# main_scheme.net
KiCad netlist of a schematic drawn in Altium Designer
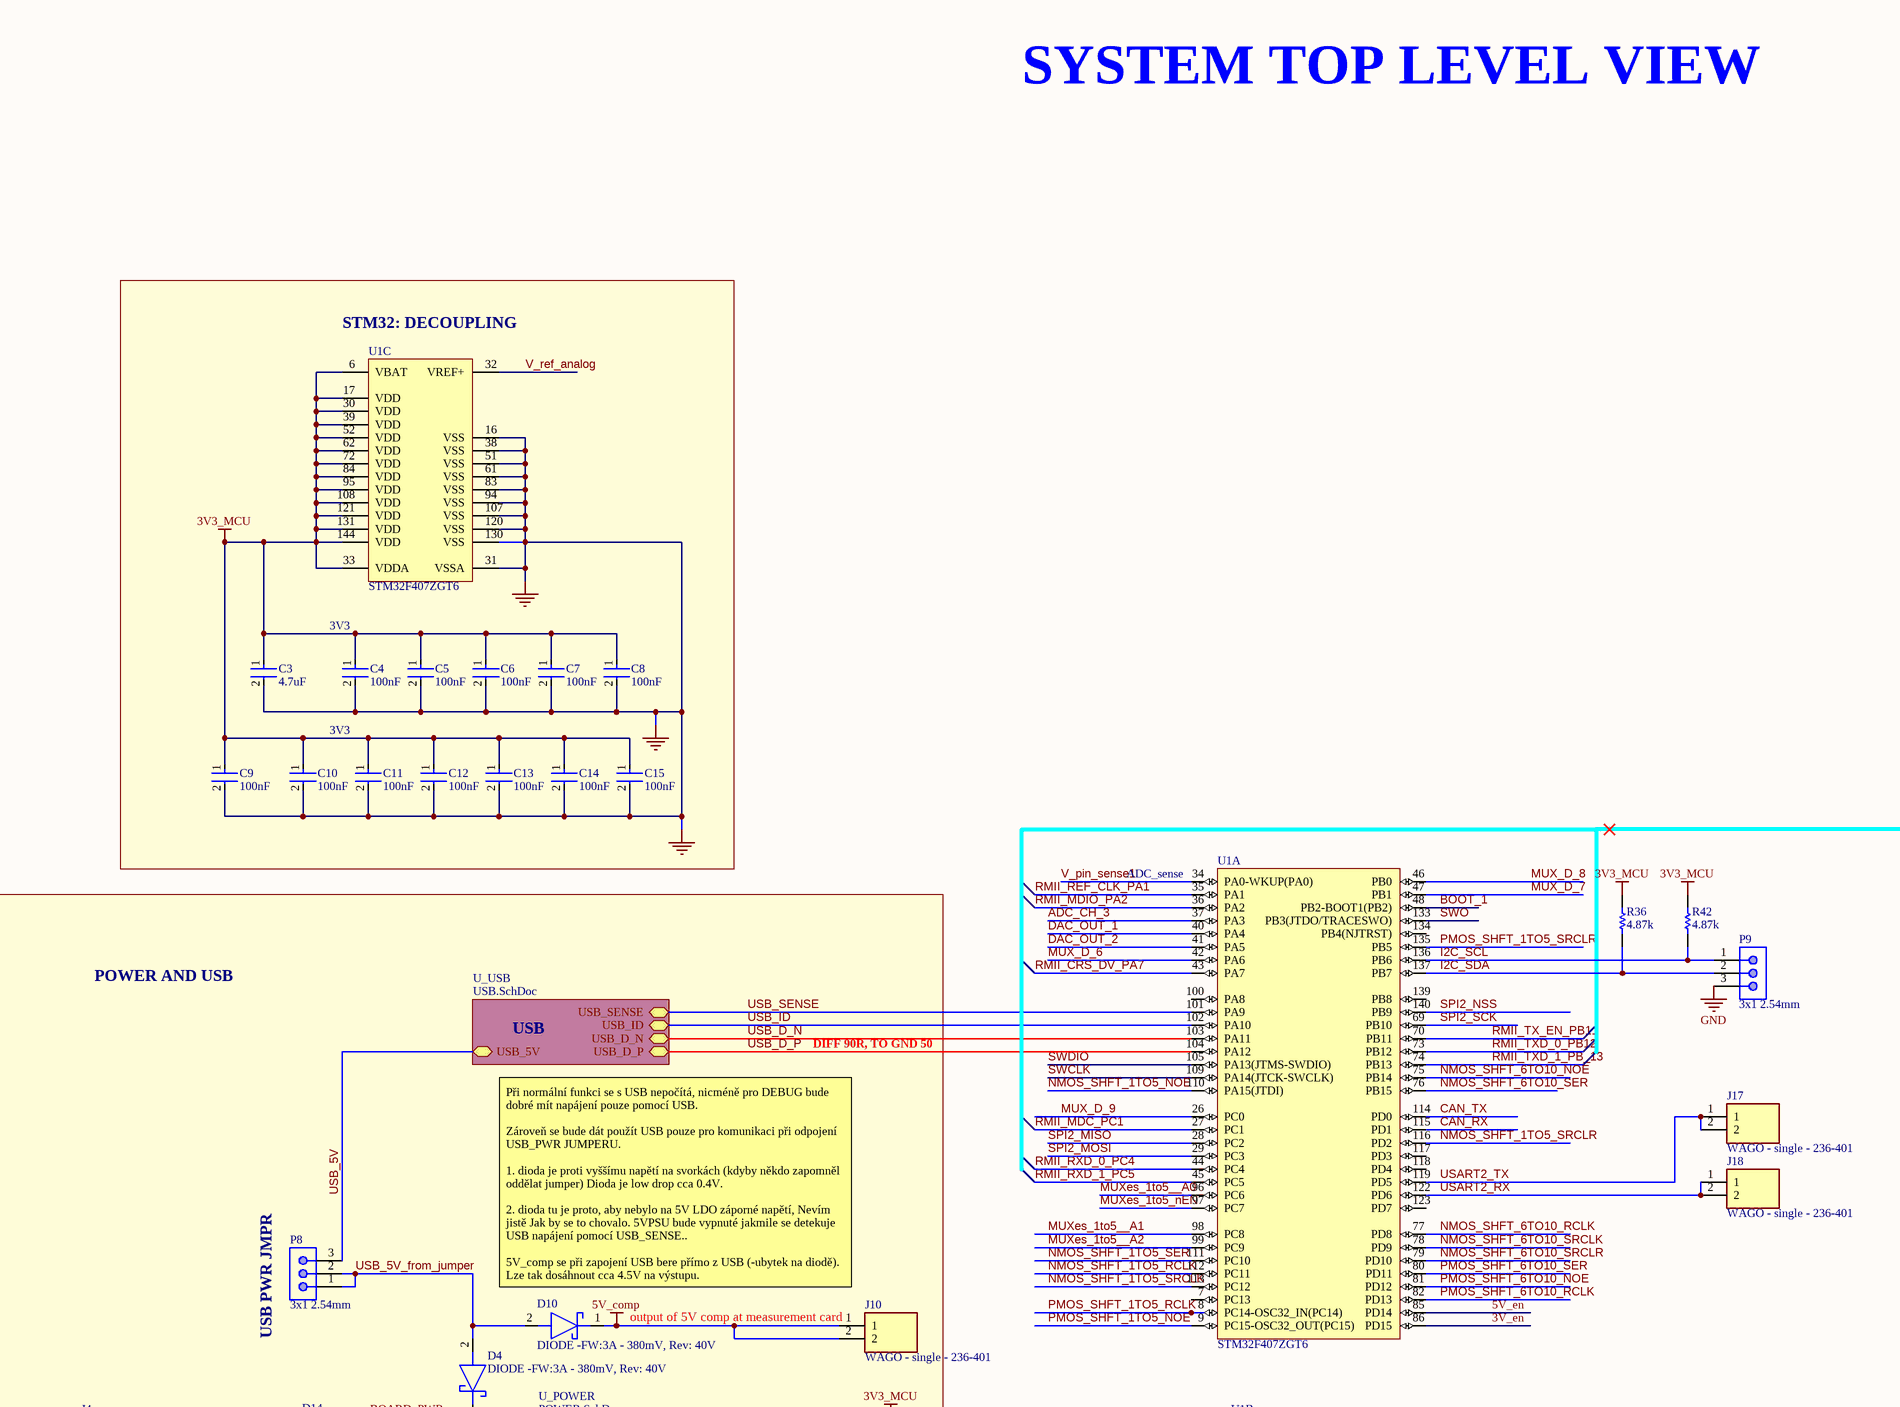
[diagram p0: main_scheme.SchDoc, top left]
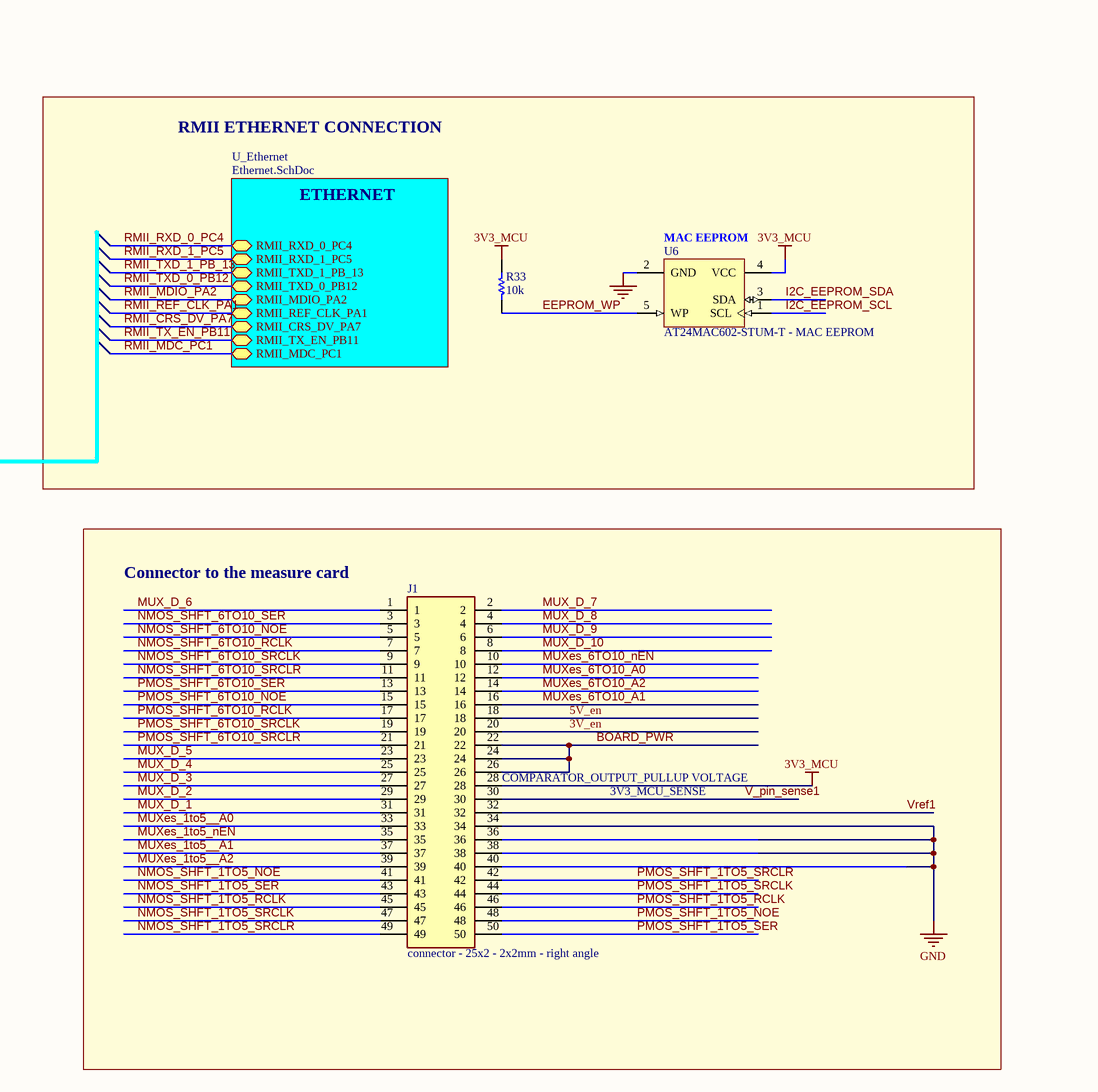
[diagram p1: main_scheme.SchDoc, top right]
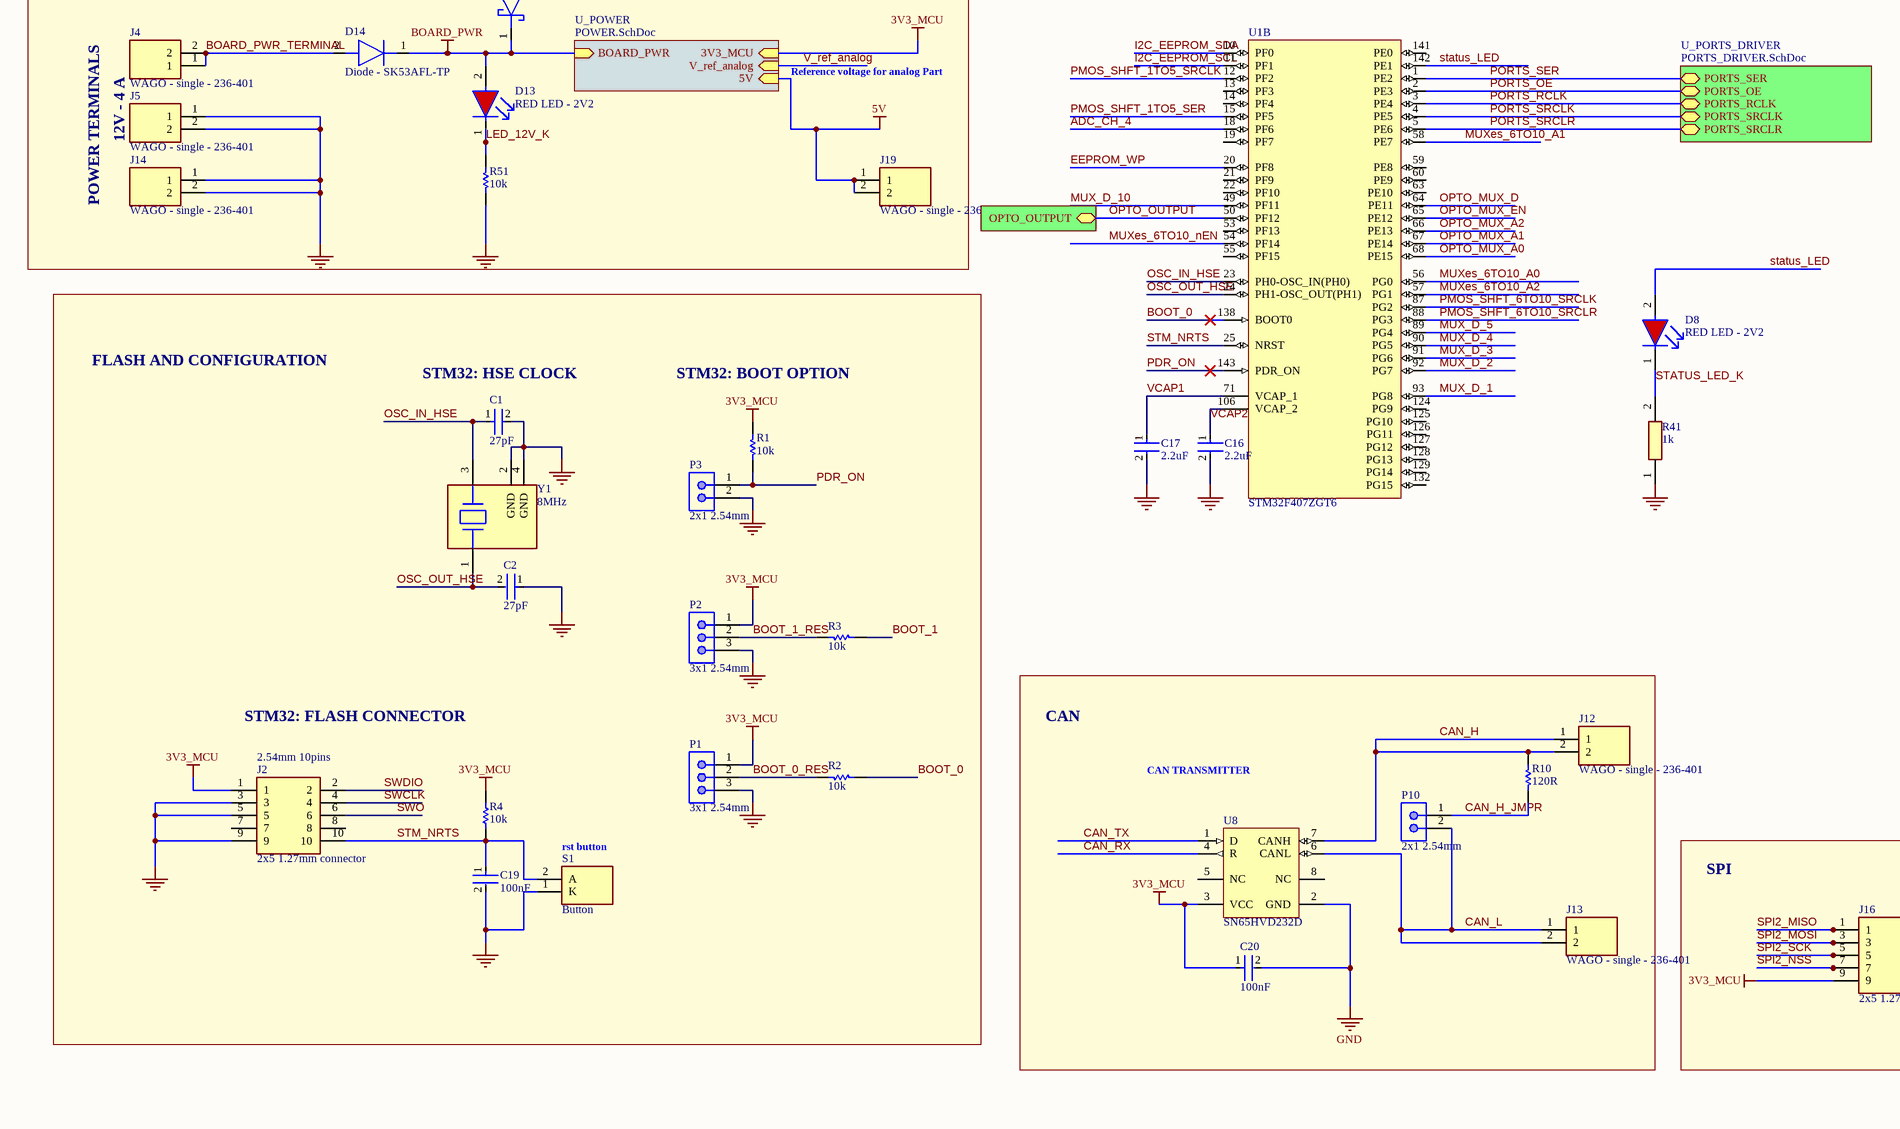
[diagram p2: main_scheme.SchDoc, bottom left]
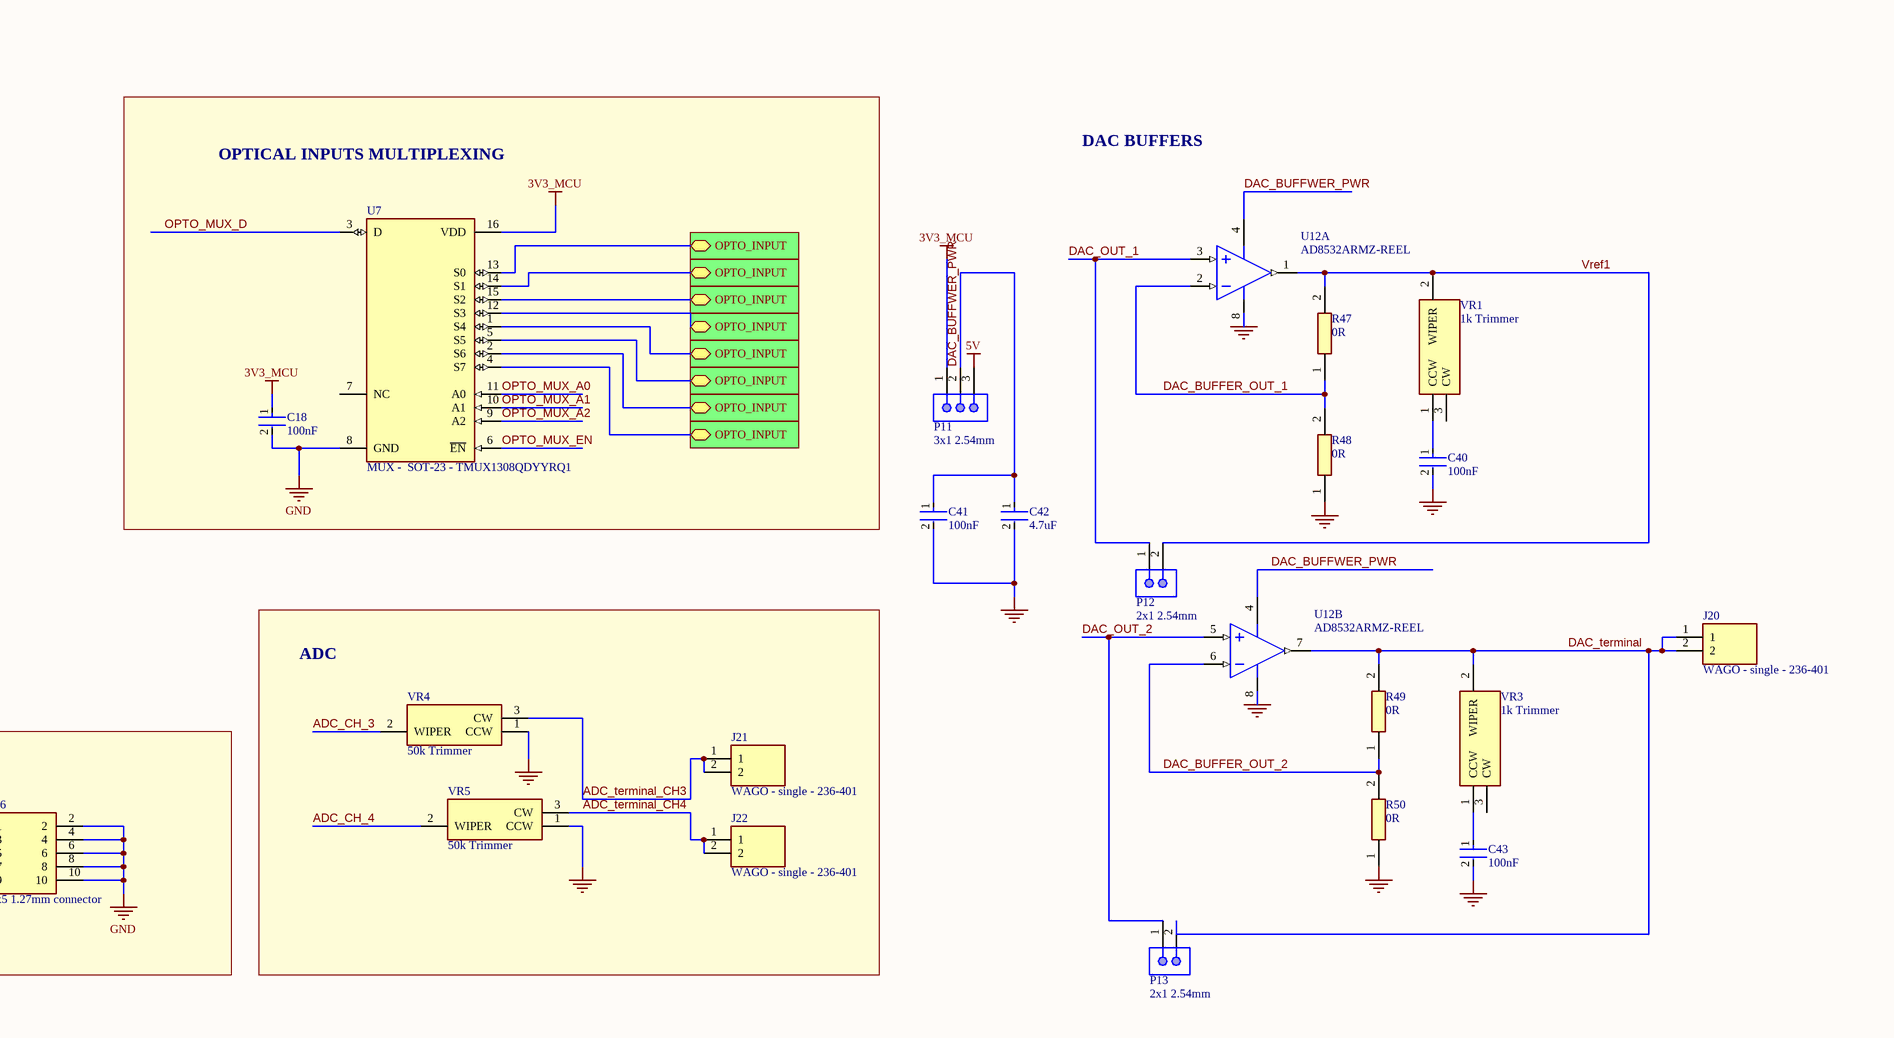
[diagram p3: main_scheme.SchDoc, bottom right]

(export (version "E")
  (design (tool "Eeschema 10.0.6"))
  (components
    (comp (ref "C1")
      (value "27pF")
      (footprint "0402 CAP")
      (description "Cap Ceramic 0402, 27pF, 25V,10%")
      (fields (field (name "PARTNUMBER") "C0402C270K3GACTU"))
      (libsource (lib "Schlib1") (part "CAP 0402 - 27pF"))
    )
    (comp (ref "C2")
      (value "27pF")
      (footprint "0402 CAP")
      (description "Cap Ceramic 0402, 27pF, 25V,10%")
      (fields (field (name "PARTNUMBER") "C0402C270K3GACTU"))
      (libsource (lib "Schlib1") (part "CAP 0402 - 27pF"))
    )
    (comp (ref "C3")
      (value "4.7uF")
      (footprint "0603-CAP")
      (description "General Purpose Ceramic Capacitor, 0603,4.7uF,35V,10%")
      (fields (field (name "PARTNUMBER") "C1608X5R1V475K080AC"))
      (libsource (lib "Schlib1") (part "CAP-0603-4.7uF"))
    )
    (comp (ref "C4")
      (value "100nF")
      (footprint "0402 CAP")
      (description "Cap Ceramic 0402,0.1uF, 25V,10%")
      (fields (field (name "PARTNUMBER") "C0402C104K3RACTU"))
      (libsource (lib "Schlib1") (part "CAP 0402 - 100nF"))
    )
    (comp (ref "C5")
      (value "100nF")
      (footprint "0402 CAP")
      (description "Cap Ceramic 0402,0.1uF, 25V,10%")
      (fields (field (name "PARTNUMBER") "C0402C104K3RACTU"))
      (libsource (lib "Schlib1") (part "CAP 0402 - 100nF"))
    )
    (comp (ref "C6")
      (value "100nF")
      (footprint "0402 CAP")
      (description "Cap Ceramic 0402,0.1uF, 25V,10%")
      (fields (field (name "PARTNUMBER") "C0402C104K3RACTU"))
      (libsource (lib "Schlib1") (part "CAP 0402 - 100nF"))
    )
    (comp (ref "C7")
      (value "100nF")
      (footprint "0402 CAP")
      (description "Cap Ceramic 0402,0.1uF, 25V,10%")
      (fields (field (name "PARTNUMBER") "C0402C104K3RACTU"))
      (libsource (lib "Schlib1") (part "CAP 0402 - 100nF"))
    )
    (comp (ref "C8")
      (value "100nF")
      (footprint "0402 CAP")
      (description "Cap Ceramic 0402,0.1uF, 25V,10%")
      (fields (field (name "PARTNUMBER") "C0402C104K3RACTU"))
      (libsource (lib "Schlib1") (part "CAP 0402 - 100nF"))
    )
    (comp (ref "C9")
      (value "100nF")
      (footprint "0402 CAP")
      (description "Cap Ceramic 0402,0.1uF, 25V,10%")
      (fields (field (name "PARTNUMBER") "C0402C104K3RACTU"))
      (libsource (lib "Schlib1") (part "CAP 0402 - 100nF"))
    )
    (comp (ref "C10")
      (value "100nF")
      (footprint "0402 CAP")
      (description "Cap Ceramic 0402,0.1uF, 25V,10%")
      (fields (field (name "PARTNUMBER") "C0402C104K3RACTU"))
      (libsource (lib "Schlib1") (part "CAP 0402 - 100nF"))
    )
    (comp (ref "C11")
      (value "100nF")
      (footprint "0402 CAP")
      (description "Cap Ceramic 0402,0.1uF, 25V,10%")
      (fields (field (name "PARTNUMBER") "C0402C104K3RACTU"))
      (libsource (lib "Schlib1") (part "CAP 0402 - 100nF"))
    )
    (comp (ref "C12")
      (value "100nF")
      (footprint "0402 CAP")
      (description "Cap Ceramic 0402,0.1uF, 25V,10%")
      (fields (field (name "PARTNUMBER") "C0402C104K3RACTU"))
      (libsource (lib "Schlib1") (part "CAP 0402 - 100nF"))
    )
    (comp (ref "C13")
      (value "100nF")
      (footprint "0402 CAP")
      (description "Cap Ceramic 0402,0.1uF, 25V,10%")
      (fields (field (name "PARTNUMBER") "C0402C104K3RACTU"))
      (libsource (lib "Schlib1") (part "CAP 0402 - 100nF"))
    )
    (comp (ref "C14")
      (value "100nF")
      (footprint "0402 CAP")
      (description "Cap Ceramic 0402,0.1uF, 25V,10%")
      (fields (field (name "PARTNUMBER") "C0402C104K3RACTU"))
      (libsource (lib "Schlib1") (part "CAP 0402 - 100nF"))
    )
    (comp (ref "C15")
      (value "100nF")
      (footprint "0402 CAP")
      (description "Cap Ceramic 0402,0.1uF, 25V,10%")
      (fields (field (name "PARTNUMBER") "C0402C104K3RACTU"))
      (libsource (lib "Schlib1") (part "CAP 0402 - 100nF"))
    )
    (comp (ref "C16")
      (value "2.2uF")
      (footprint "0603-CAP")
      (description "General Purpose Ceramic Capacitor, 0603,2.2uF,35V,10%")
      (fields (field (name "PARTNUMBER") "C1608JB1V225K080AC"))
      (libsource (lib "Schlib1") (part "CAP-0603-2.2uF"))
    )
    (comp (ref "C17")
      (value "2.2uF")
      (footprint "0603-CAP")
      (description "General Purpose Ceramic Capacitor, 0603,2.2uF,35V,10%")
      (fields (field (name "PARTNUMBER") "C1608JB1V225K080AC"))
      (libsource (lib "Schlib1") (part "CAP-0603-2.2uF"))
    )
    (comp (ref "C18")
      (value "100nF")
      (footprint "0402 CAP")
      (description "Cap Ceramic 0402,0.1uF, 25V,10%")
      (fields (field (name "PARTNUMBER") "C0402C104K3RACTU"))
      (libsource (lib "Schlib1") (part "CAP 0402 - 100nF"))
    )
    (comp (ref "C19")
      (value "100nF")
      (footprint "0402 CAP")
      (description "Cap Ceramic 0402,0.1uF, 25V,10%")
      (fields (field (name "PARTNUMBER") "C0402C104K3RACTU"))
      (libsource (lib "Schlib1") (part "CAP 0402 - 100nF"))
    )
    (comp (ref "C20")
      (value "100nF")
      (footprint "0402 CAP")
      (description "Cap Ceramic 0402,0.1uF, 25V,10%")
      (fields (field (name "PARTNUMBER") "C0402C104K3RACTU"))
      (libsource (lib "Schlib1") (part "CAP 0402 - 100nF"))
    )
    (comp (ref "C40")
      (value "100nF")
      (footprint "0402 CAP")
      (description "Cap Ceramic 0402,0.1uF, 25V,10%")
      (fields (field (name "PARTNUMBER") "C0402C104K3RACTU"))
      (libsource (lib "Schlib1") (part "CAP 0402 - 100nF"))
    )
    (comp (ref "C41")
      (value "100nF")
      (footprint "0402 CAP")
      (description "Cap Ceramic 0402,0.1uF, 25V,10%")
      (fields (field (name "PARTNUMBER") "C0402C104K3RACTU"))
      (libsource (lib "Schlib1") (part "CAP 0402 - 100nF"))
    )
    (comp (ref "C42")
      (value "4.7uF")
      (footprint "0603-CAP")
      (description "General Purpose Ceramic Capacitor, 0603,4.7uF,35V,10%")
      (fields (field (name "PARTNUMBER") "C1608X5R1V475K080AC"))
      (libsource (lib "Schlib1") (part "CAP-0603-4.7uF"))
    )
    (comp (ref "C43")
      (value "100nF")
      (footprint "0402 CAP")
      (description "Cap Ceramic 0402,0.1uF, 25V,10%")
      (fields (field (name "PARTNUMBER") "C0402C104K3RACTU"))
      (libsource (lib "Schlib1") (part "CAP 0402 - 100nF"))
    )
    (comp (ref "D4")
      (value "DIODE -FW:3A - 380mV, Rev: 40V")
      (footprint "PcbLib1:DIONM5127X229N")
      (description "Schottky DIODE -  DO-214AC-2 -FW:3A - 380mV, Rev: 40V")
      (fields (field (name "PARTNUMBER") "SSA34HE3_A/I"))
      (libsource (lib "Schlib1") (part "DIODE -FW{colon}3A - 380mV, Rev{colon} 40V"))
    )
    (comp (ref "D8")
      (value "RED LED - 2V2")
      (footprint "0603_RED_LED")
      (description "LED RED DIFFUSED 0603 SMD")
      (fields (field (name "PARTNUMBER") "SML-D12U1WT86"))
      (libsource (lib "Schlib1") (part "LED - 0603 - RED - 2V2"))
    )
    (comp (ref "D10")
      (value "DIODE -FW:3A - 380mV, Rev: 40V")
      (footprint "PcbLib1:DIONM5127X229N")
      (description "Schottky DIODE -  DO-214AC-2 -FW:3A - 380mV, Rev: 40V")
      (fields (field (name "PARTNUMBER") "SSA34HE3_A/I"))
      (libsource (lib "Schlib1") (part "DIODE -FW{colon}3A - 380mV, Rev{colon} 40V"))
    )
    (comp (ref "D13")
      (value "RED LED - 2V2")
      (footprint "0603_RED_LED")
      (description "LED RED DIFFUSED 0603 SMD")
      (fields (field (name "PARTNUMBER") "SML-D12U1WT86"))
      (libsource (lib "Schlib1") (part "LED - 0603 - RED - 2V2"))
    )
    (comp (ref "D14")
      (value "Diode - SK53AFL-TP")
      (footprint "PcbLib1:SODFL5026X120N")
      (description "Diode - 5A shottky Rectifier, Fw: 5A, 0.7V Revers: 30V, DO-221AC-2")
      (fields (field (name "PARTNUMBER") "SK53AFL-TP"))
      (libsource (lib "Schlib1") (part "Diode - SK53AFL-TP"))
    )
    (comp (ref "J1")
      (value "connector - 25x2 - 2x2mm - right angle")
      (footprint "PcbLib1:SHDRRA50W55P200_2X25_5265X640X630P_RIGHT")
      (description "Connector - connector - 25x2 - 2x2mm, SAMTEC - right angle")
      (fields (field (name "PARTNUMBER") "STMM-125-02-S-D-RA"))
      (libsource (lib "Schlib1") (part "connector - 25x2 - 2x2mm - right angle"))
    )
    (comp (ref "J2")
      (value "2x5 1.27mm connector")
      (footprint "PcbLib1:FTSH-105-XX-YYY-D")
      (description "Connector - 2x5positions -  1.27mm x1.27mm")
      (fields (field (name "PARTNUMBER") "FTSH-105-04-F-D"))
      (libsource (lib "Schlib1") (part "Connector - 2x5 -1.27 x 1.27mm"))
    )
    (comp (ref "J4")
      (value "WAGO - single - 236-401")
      (footprint "PcbLib1:WAGO-236-601")
      (description "Wago connector - PCB to wire - single - 24A 320V")
      (fields (field (name "PARTNUMBER") "236-401"))
      (libsource (lib "") (part "WAGO - single - 236-401_2"))
    )
    (comp (ref "J5")
      (value "WAGO - single - 236-401")
      (footprint "PcbLib1:WAGO-236-601")
      (description "Wago connector - PCB to wire - single - 24A 320V")
      (fields (field (name "PARTNUMBER") "236-401"))
      (libsource (lib "") (part "WAGO - single - 236-401_1"))
    )
    (comp (ref "J10")
      (value "WAGO - single - 236-401")
      (footprint "PcbLib1:WAGO-236-601")
      (description "Wago connector - PCB to wire - single - 24A 320V")
      (fields (field (name "PARTNUMBER") "236-401"))
      (libsource (lib "Schlib1") (part "WAGO - single - 236-401"))
    )
    (comp (ref "J12")
      (value "WAGO - single - 236-401")
      (footprint "PcbLib1:WAGO-236-601")
      (description "Wago connector - PCB to wire - single - 24A 320V")
      (fields (field (name "PARTNUMBER") "236-401"))
      (libsource (lib "Schlib1") (part "WAGO - single - 236-401"))
    )
    (comp (ref "J13")
      (value "WAGO - single - 236-401")
      (footprint "PcbLib1:WAGO-236-601")
      (description "Wago connector - PCB to wire - single - 24A 320V")
      (fields (field (name "PARTNUMBER") "236-401"))
      (libsource (lib "Schlib1") (part "WAGO - single - 236-401"))
    )
    (comp (ref "J14")
      (value "WAGO - single - 236-401")
      (footprint "PcbLib1:WAGO-236-601")
      (description "Wago connector - PCB to wire - single - 24A 320V")
      (fields (field (name "PARTNUMBER") "236-401"))
      (libsource (lib "") (part "WAGO - single - 236-401_1"))
    )
    (comp (ref "J16")
      (value "2x5 1.27mm connector")
      (footprint "PcbLib1:FTSH-105-XX-YYY-D")
      (description "Connector - 2x5positions -  1.27mm x1.27mm")
      (fields (field (name "PARTNUMBER") "FTSH-105-04-F-D"))
      (libsource (lib "Schlib1") (part "Connector - 2x5 -1.27 x 1.27mm"))
    )
    (comp (ref "J17")
      (value "WAGO - single - 236-401")
      (footprint "PcbLib1:WAGO-236-601")
      (description "Wago connector - PCB to wire - single - 24A 320V")
      (fields (field (name "PARTNUMBER") "236-401"))
      (libsource (lib "Schlib1") (part "WAGO - single - 236-401"))
    )
    (comp (ref "J18")
      (value "WAGO - single - 236-401")
      (footprint "PcbLib1:WAGO-236-601")
      (description "Wago connector - PCB to wire - single - 24A 320V")
      (fields (field (name "PARTNUMBER") "236-401"))
      (libsource (lib "Schlib1") (part "WAGO - single - 236-401"))
    )
    (comp (ref "J19")
      (value "WAGO - single - 236-401")
      (footprint "PcbLib1:WAGO-236-601")
      (description "Wago connector - PCB to wire - single - 24A 320V")
      (fields (field (name "PARTNUMBER") "236-401"))
      (libsource (lib "Schlib1") (part "WAGO - single - 236-401"))
    )
    (comp (ref "J20")
      (value "WAGO - single - 236-401")
      (footprint "PcbLib1:WAGO-236-601")
      (description "Wago connector - PCB to wire - single - 24A 320V")
      (fields (field (name "PARTNUMBER") "236-401"))
      (libsource (lib "Schlib1") (part "WAGO - single - 236-401"))
    )
    (comp (ref "J21")
      (value "WAGO - single - 236-401")
      (footprint "PcbLib1:WAGO-236-601")
      (description "Wago connector - PCB to wire - single - 24A 320V")
      (fields (field (name "PARTNUMBER") "236-401"))
      (libsource (lib "Schlib1") (part "WAGO - single - 236-401"))
    )
    (comp (ref "J22")
      (value "WAGO - single - 236-401")
      (footprint "PcbLib1:WAGO-236-601")
      (description "Wago connector - PCB to wire - single - 24A 320V")
      (fields (field (name "PARTNUMBER") "236-401"))
      (libsource (lib "Schlib1") (part "WAGO - single - 236-401"))
    )
    (comp (ref "P1")
      (value "3x1 2.54mm")
      (footprint "3x1 2.54mm header")
      (description "Headers & Wire Housings 3P HEADER GOLD 15u single row")
      (fields (field (name "PARTNUMBER") "5-146280-3"))
      (libsource (lib "Schlib1") (part "Header - 3x1 2.54mm"))
    )
    (comp (ref "P2")
      (value "3x1 2.54mm")
      (footprint "3x1 2.54mm header")
      (description "Headers & Wire Housings 3P HEADER GOLD 15u single row")
      (fields (field (name "PARTNUMBER") "5-146280-3"))
      (libsource (lib "Schlib1") (part "Header - 3x1 2.54mm"))
    )
    (comp (ref "P3")
      (value "2x1 2.54mm")
      (footprint "2.54mm header 2x1")
      (fields (field (name "PARTNUMBER") "5-146280-2"))
      (libsource (lib "") (part "Header - 2x1 2.54mm_1"))
    )
    (comp (ref "P8")
      (value "3x1 2.54mm")
      (footprint "3x1 2.54mm header")
      (description "Headers & Wire Housings 3P HEADER GOLD 15u single row")
      (fields (field (name "PARTNUMBER") "5-146280-3"))
      (libsource (lib "") (part "Header - 3x1 2.54mm_2"))
    )
    (comp (ref "P9")
      (value "3x1 2.54mm")
      (footprint "3x1 2.54mm header")
      (description "Headers & Wire Housings 3P HEADER GOLD 15u single row")
      (fields (field (name "PARTNUMBER") "5-146280-3"))
      (libsource (lib "") (part "Header - 3x1 2.54mm_1"))
    )
    (comp (ref "P10")
      (value "2x1 2.54mm")
      (footprint "2.54mm header 2x1")
      (fields (field (name "PARTNUMBER") "5-146280-2"))
      (libsource (lib "") (part "Header - 2x1 2.54mm_1"))
    )
    (comp (ref "P11")
      (value "3x1 2.54mm")
      (footprint "3x1 2.54mm header")
      (description "Headers & Wire Housings 3P HEADER GOLD 15u single row")
      (fields (field (name "PARTNUMBER") "5-146280-3"))
      (libsource (lib "") (part "Header - 3x1 2.54mm_2"))
    )
    (comp (ref "P12")
      (value "2x1 2.54mm")
      (footprint "2.54mm header 2x1")
      (fields (field (name "PARTNUMBER") "5-146280-2"))
      (libsource (lib "Schlib1") (part "Header - 2x1 2.54mm"))
    )
    (comp (ref "P13")
      (value "2x1 2.54mm")
      (footprint "2.54mm header 2x1")
      (fields (field (name "PARTNUMBER") "5-146280-2"))
      (libsource (lib "Schlib1") (part "Header - 2x1 2.54mm"))
    )
    (comp (ref "R1")
      (value "10k")
      (footprint "RESC1005X40X25NL05T05")
      (description "Resistor - 0402 -  10k - 5% - 125mW")
      (fields (field (name "PARTNUMBER") "RC0402JR-7W10KL"))
      (libsource (lib "Schlib1") (part "Resistor - 0402 -10k"))
    )
    (comp (ref "R2")
      (value "10k")
      (footprint "RESC1005X40X25NL05T05")
      (description "Resistor - 0402 -  10k - 5% - 125mW")
      (fields (field (name "PARTNUMBER") "RC0402JR-7W10KL"))
      (libsource (lib "Schlib1") (part "Resistor - 0402 -10k"))
    )
    (comp (ref "R3")
      (value "10k")
      (footprint "RESC1005X40X25NL05T05")
      (description "Resistor - 0402 -  10k - 5% - 125mW")
      (fields (field (name "PARTNUMBER") "RC0402JR-7W10KL"))
      (libsource (lib "Schlib1") (part "Resistor - 0402 -10k"))
    )
    (comp (ref "R4")
      (value "10k")
      (footprint "RESC1005X40X25NL05T05")
      (description "Resistor - 0402 -  10k - 5% - 125mW")
      (fields (field (name "PARTNUMBER") "RC0402JR-7W10KL"))
      (libsource (lib "Schlib1") (part "Resistor - 0402 -10k"))
    )
    (comp (ref "R10")
      (value "120R")
      (footprint "RESC1005X40X25NL05T05")
      (description "Resistor - 0402 -  120R - 1% - 100mW")
      (fields (field (name "PARTNUMBER") "ERJ-S02F1200X"))
      (libsource (lib "Schlib1") (part "Resistor - 0402 -120R"))
    )
    (comp (ref "R33")
      (value "10k")
      (footprint "RESC1005X40X25NL05T05")
      (description "Resistor - 0402 -  10k - 5% - 125mW")
      (fields (field (name "PARTNUMBER") "RC0402JR-7W10KL"))
      (libsource (lib "Schlib1") (part "Resistor - 0402 -10k"))
    )
    (comp (ref "R36")
      (value "4.87k")
      (footprint "RESC1005X40X25NL05T05")
      (description "Resistor - 0402 -  4.87k - 1% - 100mW")
      (fields (field (name "PARTNUMBER") "ERJ-2RKF4871X"))
      (libsource (lib "Schlib1") (part "Resistor - 0402 - 4.87k"))
    )
    (comp (ref "R41")
      (value "1k")
      (footprint "PcbLib1:0603- SMD resistor")
      (description "Resistor 0603 1KR 100mW 1%")
      (fields (field (name "PARTNUMBER") "RT0603FRE071KL"))
      (libsource (lib "Schlib1") (part "RESISTOR - 0603 - 1k"))
    )
    (comp (ref "R42")
      (value "4.87k")
      (footprint "RESC1005X40X25NL05T05")
      (description "Resistor - 0402 -  4.87k - 1% - 100mW")
      (fields (field (name "PARTNUMBER") "ERJ-2RKF4871X"))
      (libsource (lib "Schlib1") (part "Resistor - 0402 - 4.87k"))
    )
    (comp (ref "R47")
      (value "0R")
      (footprint "PcbLib1:0603- SMD resistor")
      (description "Resistor 0603 0R")
      (fields (field (name "PARTNUMBER") "ERJ-3GEY0R00V"))
      (libsource (lib "Schlib1") (part "RESISTOR - 0603 - 0R"))
    )
    (comp (ref "R48")
      (value "0R")
      (footprint "PcbLib1:0603- SMD resistor")
      (description "Resistor 0603 0R")
      (fields (field (name "PARTNUMBER") "ERJ-3GEY0R00V"))
      (libsource (lib "Schlib1") (part "RESISTOR - 0603 - 0R"))
    )
    (comp (ref "R49")
      (value "0R")
      (footprint "PcbLib1:0603- SMD resistor")
      (description "Resistor 0603 0R")
      (fields (field (name "PARTNUMBER") "ERJ-3GEY0R00V"))
      (libsource (lib "Schlib1") (part "RESISTOR - 0603 - 0R"))
    )
    (comp (ref "R50")
      (value "0R")
      (footprint "PcbLib1:0603- SMD resistor")
      (description "Resistor 0603 0R")
      (fields (field (name "PARTNUMBER") "ERJ-3GEY0R00V"))
      (libsource (lib "Schlib1") (part "RESISTOR - 0603 - 0R"))
    )
    (comp (ref "R51")
      (value "10k")
      (footprint "RESC1005X40X25NL05T05")
      (description "Resistor - 0402 -  10k - 5% - 125mW")
      (fields (field (name "PARTNUMBER") "RC0402JR-7W10KL"))
      (libsource (lib "Schlib1") (part "Resistor - 0402 -10k"))
    )
    (comp (ref "S1")
      (value "Button")
      (footprint "PcbLib1:B3U-1000P")
      (description "Push button - 2poles,  L:2.5mm, W:3mm, H:1.2mm, 12VDC - 50mA")
      (fields (field (name "PARTNUMBER") "B3U-1000P"))
      (libsource (lib "Schlib1") (part "Button - smd -2 poles"))
    )
    (comp (ref "U1")
      (value "STM32F407ZGT6")
      (footprint "STM-LQFP144_L")
      (libsource (lib "Schlib1") (part "STM32F407ZGT6"))
    )
    (comp (ref "U6")
      (value "AT24MAC602-STUM-T - MAC EEPROM")
      (footprint "ATML-5TS1_L")
      (fields (field (name "PARTNUMBER") "AT24MAC602-STUM-T"))
      (libsource (lib "Schlib1") (part "MAC_EEPROM_I2C"))
    )
    (comp (ref "U7")
      (value "MUX -  SOT-23 - TMUX1308QDYYRQ1")
      (footprint "FP-DYY0016A-MFG")
      (fields (field (name "PARTNUMBER") "TMUX1308QDYYRQ1"))
      (libsource (lib "Schlib1") (part "MUX -  SOT-23 - TMUX1308QDYYRQ1"))
    )
    (comp (ref "U8")
      (value "SN65HVD232D")
      (footprint "D0008A_L")
      (description "3.3 V CAN Transceiver, 17 mA, -40 to 85 degC, 8-pin SOIC (D), Green (RoHS & no Sb/Br)")
      (libsource (lib "Schlib1") (part "CAN - PHY - SN65HVD232D"))
    )
    (comp (ref "U12")
      (value "AD8532ARMZ-REEL")
      (footprint "ADI-RM-8_L")
      (libsource (lib "Schlib1") (part "OPAMP - 2CH AD8532ARMZ-REEL"))
    )
    (comp (ref "VR1")
      (value "1k Trimmer")
      (footprint "PcbLib1:TC33X2503E")
      (description "Variable Resistor Trimmer - 1k - 25% -100mW - single turn")
      (fields (field (name "PARTNUMBER") "TC33X-2-102E"))
      (libsource (lib "Schlib1") (part "TRIMMER - 1k -100mW"))
    )
    (comp (ref "VR3")
      (value "1k Trimmer")
      (footprint "PcbLib1:TC33X2503E")
      (description "Variable Resistor Trimmer - 1k - 25% -100mW - single turn")
      (fields (field (name "PARTNUMBER") "TC33X-2-102E"))
      (libsource (lib "Schlib1") (part "TRIMMER - 1k -100mW"))
    )
    (comp (ref "VR4")
      (value "50k Trimmer")
      (footprint "PcbLib1:TC33X2503E")
      (description "Variable Resistor Trimmer - 50k - 25% -100mW - single turn")
      (fields (field (name "PARTNUMBER") "TC33X-2-102E"))
      (libsource (lib "Schlib1") (part "TRIMMER - 50k -100mW"))
    )
    (comp (ref "VR5")
      (value "50k Trimmer")
      (footprint "PcbLib1:TC33X2503E")
      (description "Variable Resistor Trimmer - 50k - 25% -100mW - single turn")
      (fields (field (name "PARTNUMBER") "TC33X-2-102E"))
      (libsource (lib "Schlib1") (part "TRIMMER - 50k -100mW"))
    )
    (comp (ref "Y1")
      (value "8MHz")
      (footprint "4_pin_OSCILATOR")
      (description "Crystal 8MHz ±10ppm CL=18pF SMD-4 5mm x 3.2mm")
      (fields (field (name "PARTNUMBER") "ABM3B-8.000MHZ-D2-T"))
      (libsource (lib "Schlib1") (part "8MHz-Osc"))
    )
  )
  (nets
    (net (code "1") (name "/3V_en") (class "Default")
      (node (ref "J1") (pin "20") (pinfunction "20_20") (pintype "passive"))
      (node (ref "U1") (pin "86") (pinfunction "PD15_86") (pintype "bidirectional"))
    )
    (net (code "2") (name "/5V_en") (class "Default")
      (node (ref "J1") (pin "18") (pinfunction "18_18") (pintype "passive"))
      (node (ref "U1") (pin "85") (pinfunction "PD14_85") (pintype "bidirectional"))
    )
    (net (code "3") (name "/ADC_CH_3") (class "Default")
      (node (ref "U1") (pin "37") (pinfunction "PA3_37") (pintype "bidirectional"))
      (node (ref "VR4") (pin "2") (pinfunction "WIPER_2") (pintype "passive"))
    )
    (net (code "4") (name "/ADC_CH_4") (class "Default")
      (node (ref "U1") (pin "18") (pinfunction "PF6_18") (pintype "bidirectional"))
      (node (ref "VR5") (pin "2") (pinfunction "WIPER_2") (pintype "passive"))
    )
    (net (code "5") (name "/ADC_terminal_CH3") (class "Default")
      (node (ref "J21") (pin "1") (pinfunction "1_1") (pintype "passive"))
      (node (ref "J21") (pin "2") (pinfunction "2_2") (pintype "passive"))
      (node (ref "VR4") (pin "3") (pinfunction "CW_3") (pintype "passive"))
    )
    (net (code "6") (name "/ADC_terminal_CH4") (class "Default")
      (node (ref "J22") (pin "1") (pinfunction "1_1") (pintype "passive"))
      (node (ref "J22") (pin "2") (pinfunction "2_2") (pintype "passive"))
      (node (ref "VR5") (pin "3") (pinfunction "CW_3") (pintype "passive"))
    )
    (net (code "7") (name "/BOARD_PWR_TERMINAL") (class "Default")
      (node (ref "D14") (pin "2") (pinfunction "A_2") (pintype "passive"))
      (node (ref "J4") (pin "1") (pinfunction "1_1") (pintype "passive"))
      (node (ref "J4") (pin "2") (pinfunction "2_2") (pintype "passive"))
    )
    (net (code "8") (name "/BOOT_0") (class "Default")
      (node (ref "R2") (pin "2") (pinfunction "2_2") (pintype "passive"))
      (node (ref "U1") (pin "138") (pinfunction "BOOT0_138") (pintype "input"))
    )
    (net (code "9") (name "/BOOT_0_RES") (class "Default")
      (node (ref "P1") (pin "2") (pinfunction "2_2") (pintype "passive"))
      (node (ref "R2") (pin "1") (pinfunction "1_1") (pintype "passive"))
    )
    (net (code "10") (name "/BOOT_1") (class "Default")
      (node (ref "R3") (pin "2") (pinfunction "2_2") (pintype "passive"))
      (node (ref "U1") (pin "48") (pinfunction "PB2-BOOT1(PB2)_48") (pintype "bidirectional"))
    )
    (net (code "11") (name "/BOOT_1_RES") (class "Default")
      (node (ref "P2") (pin "2") (pinfunction "2_2") (pintype "passive"))
      (node (ref "R3") (pin "1") (pinfunction "1_1") (pintype "passive"))
    )
    (net (code "12") (name "/CAN_H") (class "Default")
      (node (ref "J12") (pin "1") (pinfunction "1_1") (pintype "passive"))
      (node (ref "J12") (pin "2") (pinfunction "2_2") (pintype "passive"))
      (node (ref "R10") (pin "2") (pinfunction "2_2") (pintype "passive"))
      (node (ref "U8") (pin "7") (pinfunction "CANH_7") (pintype "bidirectional"))
    )
    (net (code "13") (name "/CAN_H_JMPR") (class "Default")
      (node (ref "P10") (pin "1") (pinfunction "1_1") (pintype "passive"))
      (node (ref "R10") (pin "1") (pinfunction "1_1") (pintype "passive"))
    )
    (net (code "14") (name "/CAN_L") (class "Default")
      (node (ref "J13") (pin "1") (pinfunction "1_1") (pintype "passive"))
      (node (ref "J13") (pin "2") (pinfunction "2_2") (pintype "passive"))
      (node (ref "P10") (pin "2") (pinfunction "2_2") (pintype "passive"))
      (node (ref "U8") (pin "6") (pinfunction "CANL_6") (pintype "bidirectional"))
    )
    (net (code "15") (name "/CAN_RX") (class "Default")
      (node (ref "U1") (pin "115") (pinfunction "PD1_115") (pintype "bidirectional"))
      (node (ref "U8") (pin "4") (pinfunction "R_4") (pintype "output"))
    )
    (net (code "16") (name "/CAN_TX") (class "Default")
      (node (ref "U1") (pin "114") (pinfunction "PD0_114") (pintype "bidirectional"))
      (node (ref "U8") (pin "1") (pinfunction "D_1") (pintype "input"))
    )
    (net (code "17") (name "/DAC_BUFFER_OUT_1") (class "Default")
      (node (ref "R47") (pin "1") (pinfunction "1_1") (pintype "passive"))
      (node (ref "R48") (pin "2") (pinfunction "2_2") (pintype "passive"))
      (node (ref "U12") (pin "2") (pinfunction "-IN_A_2") (pintype "input"))
    )
    (net (code "18") (name "/DAC_BUFFER_OUT_2") (class "Default")
      (node (ref "R49") (pin "1") (pinfunction "1_1") (pintype "passive"))
      (node (ref "R50") (pin "2") (pinfunction "2_2") (pintype "passive"))
      (node (ref "U12") (pin "6") (pinfunction "-IN_B_6") (pintype "input"))
    )
    (net (code "19") (name "/DAC_BUFFWER_PWR") (class "Default")
      (node (ref "C41") (pin "1") (pinfunction "1_1") (pintype "passive"))
      (node (ref "C42") (pin "1") (pinfunction "1_1") (pintype "passive"))
      (node (ref "P11") (pin "2") (pinfunction "2_2") (pintype "passive"))
      (node (ref "U12") (pin "4") (pinfunction "-V_4") (pintype "power_in"))
    )
    (net (code "20") (name "/DAC_OUT_1") (class "Default")
      (node (ref "P12") (pin "1") (pinfunction "1_1") (pintype "passive"))
      (node (ref "U1") (pin "40") (pinfunction "PA4_40") (pintype "bidirectional"))
      (node (ref "U12") (pin "3") (pinfunction "+IN_A_3") (pintype "input"))
    )
    (net (code "21") (name "/DAC_OUT_2") (class "Default")
      (node (ref "P13") (pin "1") (pinfunction "1_1") (pintype "passive"))
      (node (ref "U1") (pin "41") (pinfunction "PA5_41") (pintype "bidirectional"))
      (node (ref "U12") (pin "5") (pinfunction "+IN_B_5") (pintype "input"))
    )
    (net (code "22") (name "/DAC_terminal") (class "Default")
      (node (ref "J20") (pin "1") (pinfunction "1_1") (pintype "passive"))
      (node (ref "J20") (pin "2") (pinfunction "2_2") (pintype "passive"))
      (node (ref "P13") (pin "2") (pinfunction "2_2") (pintype "passive"))
      (node (ref "R49") (pin "2") (pinfunction "2_2") (pintype "passive"))
      (node (ref "U12") (pin "7") (pinfunction "OUT_B_7") (pintype "output"))
      (node (ref "VR3") (pin "2") (pinfunction "WIPER_2") (pintype "passive"))
    )
    (net (code "23") (name "/EEPROM_WP") (class "Default")
      (node (ref "R33") (pin "2") (pinfunction "2_2") (pintype "passive"))
      (node (ref "U1") (pin "20") (pinfunction "PF8_20") (pintype "bidirectional"))
      (node (ref "U6") (pin "5") (pinfunction "WP_5") (pintype "input"))
    )
    (net (code "24") (name "/I2C_EEPROM_SCL") (class "Default")
      (node (ref "U1") (pin "11") (pinfunction "PF1_11") (pintype "bidirectional"))
      (node (ref "U6") (pin "1") (pinfunction "SCL_1") (pintype "input"))
    )
    (net (code "25") (name "/I2C_EEPROM_SDA") (class "Default")
      (node (ref "U1") (pin "10") (pinfunction "PF0_10") (pintype "bidirectional"))
      (node (ref "U6") (pin "3") (pinfunction "SDA_3") (pintype "bidirectional"))
    )
    (net (code "26") (name "/I2C_SCL") (class "Default")
      (node (ref "P9") (pin "1") (pinfunction "1_1") (pintype "passive"))
      (node (ref "R42") (pin "2") (pinfunction "2_2") (pintype "passive"))
      (node (ref "U1") (pin "136") (pinfunction "PB6_136") (pintype "bidirectional"))
    )
    (net (code "27") (name "/I2C_SDA") (class "Default")
      (node (ref "P9") (pin "2") (pinfunction "2_2") (pintype "passive"))
      (node (ref "R36") (pin "2") (pinfunction "2_2") (pintype "passive"))
      (node (ref "U1") (pin "137") (pinfunction "PB7_137") (pintype "bidirectional"))
    )
    (net (code "28") (name "/LED_12V_K") (class "Default")
      (node (ref "D13") (pin "1") (pinfunction "C_1") (pintype "passive"))
      (node (ref "R51") (pin "2") (pinfunction "2_2") (pintype "passive"))
    )
    (net (code "29") (name "/MUX_D_1") (class "Default")
      (node (ref "J1") (pin "31") (pinfunction "31_31") (pintype "passive"))
      (node (ref "U1") (pin "93") (pinfunction "PG8_93") (pintype "bidirectional"))
    )
    (net (code "30") (name "/MUX_D_2") (class "Default")
      (node (ref "J1") (pin "29") (pinfunction "29_29") (pintype "passive"))
      (node (ref "U1") (pin "92") (pinfunction "PG7_92") (pintype "bidirectional"))
    )
    (net (code "31") (name "/MUX_D_3") (class "Default")
      (node (ref "J1") (pin "27") (pinfunction "27_27") (pintype "passive"))
      (node (ref "U1") (pin "91") (pinfunction "PG6_91") (pintype "bidirectional"))
    )
    (net (code "32") (name "/MUX_D_4") (class "Default")
      (node (ref "J1") (pin "25") (pinfunction "25_25") (pintype "passive"))
      (node (ref "U1") (pin "90") (pinfunction "PG5_90") (pintype "bidirectional"))
    )
    (net (code "33") (name "/MUX_D_5") (class "Default")
      (node (ref "J1") (pin "23") (pinfunction "23_23") (pintype "passive"))
      (node (ref "U1") (pin "89") (pinfunction "PG4_89") (pintype "bidirectional"))
    )
    (net (code "34") (name "/MUX_D_6") (class "Default")
      (node (ref "J1") (pin "1") (pinfunction "1_1") (pintype "passive"))
      (node (ref "U1") (pin "42") (pinfunction "PA6_42") (pintype "bidirectional"))
    )
    (net (code "35") (name "/MUX_D_7") (class "Default")
      (node (ref "J1") (pin "2") (pinfunction "2_2") (pintype "passive"))
      (node (ref "U1") (pin "47") (pinfunction "PB1_47") (pintype "bidirectional"))
    )
    (net (code "36") (name "/MUX_D_8") (class "Default")
      (node (ref "J1") (pin "4") (pinfunction "4_4") (pintype "passive"))
      (node (ref "U1") (pin "46") (pinfunction "PB0_46") (pintype "bidirectional"))
    )
    (net (code "37") (name "/MUX_D_9") (class "Default")
      (node (ref "J1") (pin "6") (pinfunction "6_6") (pintype "passive"))
      (node (ref "U1") (pin "26") (pinfunction "PC0_26") (pintype "bidirectional"))
    )
    (net (code "38") (name "/MUX_D_10") (class "Default")
      (node (ref "J1") (pin "8") (pinfunction "8_8") (pintype "passive"))
      (node (ref "U1") (pin "49") (pinfunction "PF11_49") (pintype "bidirectional"))
    )
    (net (code "39") (name "/MUXes_1to5__A0") (class "Default")
      (node (ref "J1") (pin "33") (pinfunction "33_33") (pintype "passive"))
      (node (ref "U1") (pin "96") (pinfunction "PC6_96") (pintype "bidirectional"))
    )
    (net (code "40") (name "/MUXes_1to5__A1") (class "Default")
      (node (ref "J1") (pin "37") (pinfunction "37_37") (pintype "passive"))
      (node (ref "U1") (pin "98") (pinfunction "PC8_98") (pintype "bidirectional"))
    )
    (net (code "41") (name "/MUXes_1to5__A2") (class "Default")
      (node (ref "J1") (pin "39") (pinfunction "39_39") (pintype "passive"))
      (node (ref "U1") (pin "99") (pinfunction "PC9_99") (pintype "bidirectional"))
    )
    (net (code "42") (name "/MUXes_1to5_nEN") (class "Default")
      (node (ref "J1") (pin "35") (pinfunction "35_35") (pintype "passive"))
      (node (ref "U1") (pin "97") (pinfunction "PC7_97") (pintype "bidirectional"))
    )
    (net (code "43") (name "/MUXes_6TO10_A0") (class "Default")
      (node (ref "J1") (pin "12") (pinfunction "12_12") (pintype "passive"))
      (node (ref "U1") (pin "56") (pinfunction "PG0_56") (pintype "bidirectional"))
    )
    (net (code "44") (name "/MUXes_6TO10_A1") (class "Default")
      (node (ref "J1") (pin "16") (pinfunction "16_16") (pintype "passive"))
      (node (ref "U1") (pin "58") (pinfunction "PE7_58") (pintype "bidirectional"))
    )
    (net (code "45") (name "/MUXes_6TO10_A2") (class "Default")
      (node (ref "J1") (pin "14") (pinfunction "14_14") (pintype "passive"))
      (node (ref "U1") (pin "57") (pinfunction "PG1_57") (pintype "bidirectional"))
    )
    (net (code "46") (name "/MUXes_6TO10_nEN") (class "Default")
      (node (ref "J1") (pin "10") (pinfunction "10_10") (pintype "passive"))
      (node (ref "U1") (pin "54") (pinfunction "PF14_54") (pintype "bidirectional"))
    )
    (net (code "47") (name "/NMOS_SHFT_1TO5_NOE") (class "Default")
      (node (ref "J1") (pin "41") (pinfunction "41_41") (pintype "passive"))
      (node (ref "U1") (pin "110") (pinfunction "PA15(JTDI)_110") (pintype "bidirectional"))
    )
    (net (code "48") (name "/NMOS_SHFT_1TO5_RCLK") (class "Default")
      (node (ref "J1") (pin "45") (pinfunction "45_45") (pintype "passive"))
      (node (ref "U1") (pin "112") (pinfunction "PC11_112") (pintype "bidirectional"))
    )
    (net (code "49") (name "/NMOS_SHFT_1TO5_SER") (class "Default")
      (node (ref "J1") (pin "43") (pinfunction "43_43") (pintype "passive"))
      (node (ref "U1") (pin "111") (pinfunction "PC10_111") (pintype "bidirectional"))
    )
    (net (code "50") (name "/NMOS_SHFT_1TO5_SRCLK") (class "Default")
      (node (ref "J1") (pin "47") (pinfunction "47_47") (pintype "passive"))
      (node (ref "U1") (pin "113") (pinfunction "PC12_113") (pintype "bidirectional"))
    )
    (net (code "51") (name "/NMOS_SHFT_1TO5_SRCLR") (class "Default")
      (node (ref "J1") (pin "49") (pinfunction "49_49") (pintype "passive"))
      (node (ref "U1") (pin "116") (pinfunction "PD2_116") (pintype "bidirectional"))
    )
    (net (code "52") (name "/NMOS_SHFT_6TO10_NOE") (class "Default")
      (node (ref "J1") (pin "5") (pinfunction "5_5") (pintype "passive"))
      (node (ref "U1") (pin "75") (pinfunction "PB14_75") (pintype "bidirectional"))
    )
    (net (code "53") (name "/NMOS_SHFT_6TO10_RCLK") (class "Default")
      (node (ref "J1") (pin "7") (pinfunction "7_7") (pintype "passive"))
      (node (ref "U1") (pin "77") (pinfunction "PD8_77") (pintype "bidirectional"))
    )
    (net (code "54") (name "/NMOS_SHFT_6TO10_SER") (class "Default")
      (node (ref "J1") (pin "3") (pinfunction "3_3") (pintype "passive"))
      (node (ref "U1") (pin "76") (pinfunction "PB15_76") (pintype "bidirectional"))
    )
    (net (code "55") (name "/NMOS_SHFT_6TO10_SRCLK") (class "Default")
      (node (ref "J1") (pin "9") (pinfunction "9_9") (pintype "passive"))
      (node (ref "U1") (pin "78") (pinfunction "PD9_78") (pintype "bidirectional"))
    )
    (net (code "56") (name "/NMOS_SHFT_6TO10_SRCLR") (class "Default")
      (node (ref "J1") (pin "11") (pinfunction "11_11") (pintype "passive"))
      (node (ref "U1") (pin "79") (pinfunction "PD10_79") (pintype "bidirectional"))
    )
    (net (code "57") (name "/OPTO_INPUT") (class "Default")
      (node (ref "U7") (pin "4") (pinfunction "S7_4") (pintype "bidirectional"))
    )
    (net (code "58") (name "/OPTO_INPUT_1") (class "Default")
      (node (ref "U7") (pin "13") (pinfunction "S0_13") (pintype "bidirectional"))
    )
    (net (code "59") (name "/OPTO_INPUT_2") (class "Default")
      (node (ref "U7") (pin "15") (pinfunction "S2_15") (pintype "bidirectional"))
    )
    (net (code "60") (name "/OPTO_INPUT_3") (class "Default")
      (node (ref "U7") (pin "12") (pinfunction "S3_12") (pintype "bidirectional"))
    )
    (net (code "61") (name "/OPTO_INPUT_4") (class "Default")
      (node (ref "U7") (pin "1") (pinfunction "S4_1") (pintype "bidirectional"))
    )
    (net (code "62") (name "/OPTO_INPUT_5") (class "Default")
      (node (ref "U7") (pin "5") (pinfunction "S5_5") (pintype "bidirectional"))
    )
    (net (code "63") (name "/OPTO_INPUT_6") (class "Default")
      (node (ref "U7") (pin "2") (pinfunction "S6_2") (pintype "bidirectional"))
    )
    (net (code "64") (name "/OPTO_INPUT_7") (class "Default")
      (node (ref "U7") (pin "14") (pinfunction "S1_14") (pintype "bidirectional"))
    )
    (net (code "65") (name "/OPTO_MUX_A0") (class "Default")
      (node (ref "U1") (pin "68") (pinfunction "PE15_68") (pintype "bidirectional"))
      (node (ref "U7") (pin "11") (pinfunction "A0_11") (pintype "input"))
    )
    (net (code "66") (name "/OPTO_MUX_A1") (class "Default")
      (node (ref "U1") (pin "67") (pinfunction "PE14_67") (pintype "bidirectional"))
      (node (ref "U7") (pin "10") (pinfunction "A1_10") (pintype "input"))
    )
    (net (code "67") (name "/OPTO_MUX_A2") (class "Default")
      (node (ref "U1") (pin "66") (pinfunction "PE13_66") (pintype "bidirectional"))
      (node (ref "U7") (pin "9") (pinfunction "A2_9") (pintype "input"))
    )
    (net (code "68") (name "/OPTO_MUX_D") (class "Default")
      (node (ref "U1") (pin "64") (pinfunction "PE11_64") (pintype "bidirectional"))
      (node (ref "U7") (pin "3") (pinfunction "D_3") (pintype "bidirectional"))
    )
    (net (code "69") (name "/OPTO_MUX_EN") (class "Default")
      (node (ref "U1") (pin "65") (pinfunction "PE12_65") (pintype "bidirectional"))
      (node (ref "U7") (pin "6") (pinfunction "~{EN}_6") (pintype "input"))
    )
    (net (code "70") (name "/OPTO_OUTPUT") (class "Default")
      (node (ref "U1") (pin "50") (pinfunction "PF12_50") (pintype "bidirectional"))
    )
    (net (code "71") (name "/OSC_IN_HSE") (class "Default")
      (node (ref "C1") (pin "1") (pinfunction "1_1") (pintype "passive"))
      (node (ref "U1") (pin "23") (pinfunction "PH0-OSC_IN(PH0)_23") (pintype "bidirectional"))
      (node (ref "Y1") (pin "3") (pinfunction "3_3") (pintype "passive"))
    )
    (net (code "72") (name "/OSC_OUT_HSE") (class "Default")
      (node (ref "C2") (pin "2") (pinfunction "2_2") (pintype "passive"))
      (node (ref "U1") (pin "24") (pinfunction "PH1-OSC_OUT(PH1)_24") (pintype "bidirectional"))
      (node (ref "Y1") (pin "1") (pinfunction "1_1") (pintype "passive"))
    )
    (net (code "73") (name "/PDR_ON") (class "Default")
      (node (ref "P3") (pin "1") (pinfunction "1_1") (pintype "passive"))
      (node (ref "R1") (pin "2") (pinfunction "2_2") (pintype "passive"))
      (node (ref "U1") (pin "143") (pinfunction "PDR_ON_143") (pintype "input"))
    )
    (net (code "74") (name "/PMOS_SHFT_1TO5_NOE") (class "Default")
      (node (ref "J1") (pin "48") (pinfunction "48_48") (pintype "passive"))
      (node (ref "U1") (pin "9") (pinfunction "PC15-OSC32_OUT(PC15)_9") (pintype "bidirectional"))
    )
    (net (code "75") (name "/PMOS_SHFT_1TO5_RCLK") (class "Default")
      (node (ref "J1") (pin "46") (pinfunction "46_46") (pintype "passive"))
      (node (ref "U1") (pin "8") (pinfunction "PC14-OSC32_IN(PC14)_8") (pintype "bidirectional"))
    )
    (net (code "76") (name "/PMOS_SHFT_1TO5_SER") (class "Default")
      (node (ref "J1") (pin "50") (pinfunction "50_50") (pintype "passive"))
      (node (ref "U1") (pin "15") (pinfunction "PF5_15") (pintype "bidirectional"))
    )
    (net (code "77") (name "/PMOS_SHFT_1TO5_SRCLK") (class "Default")
      (node (ref "J1") (pin "44") (pinfunction "44_44") (pintype "passive"))
      (node (ref "U1") (pin "12") (pinfunction "PF2_12") (pintype "bidirectional"))
    )
    (net (code "78") (name "/PMOS_SHFT_1TO5_SRCLR") (class "Default")
      (node (ref "J1") (pin "42") (pinfunction "42_42") (pintype "passive"))
      (node (ref "U1") (pin "135") (pinfunction "PB5_135") (pintype "bidirectional"))
    )
    (net (code "79") (name "/PMOS_SHFT_6TO10_NOE") (class "Default")
      (node (ref "J1") (pin "15") (pinfunction "15_15") (pintype "passive"))
      (node (ref "U1") (pin "81") (pinfunction "PD12_81") (pintype "bidirectional"))
    )
    (net (code "80") (name "/PMOS_SHFT_6TO10_RCLK") (class "Default")
      (node (ref "J1") (pin "17") (pinfunction "17_17") (pintype "passive"))
      (node (ref "U1") (pin "82") (pinfunction "PD13_82") (pintype "bidirectional"))
    )
    (net (code "81") (name "/PMOS_SHFT_6TO10_SER") (class "Default")
      (node (ref "J1") (pin "13") (pinfunction "13_13") (pintype "passive"))
      (node (ref "U1") (pin "80") (pinfunction "PD11_80") (pintype "bidirectional"))
    )
    (net (code "82") (name "/PMOS_SHFT_6TO10_SRCLK") (class "Default")
      (node (ref "J1") (pin "19") (pinfunction "19_19") (pintype "passive"))
      (node (ref "U1") (pin "87") (pinfunction "PG2_87") (pintype "bidirectional"))
    )
    (net (code "83") (name "/PMOS_SHFT_6TO10_SRCLR") (class "Default")
      (node (ref "J1") (pin "21") (pinfunction "21_21") (pintype "passive"))
      (node (ref "U1") (pin "88") (pinfunction "PG3_88") (pintype "bidirectional"))
    )
    (net (code "84") (name "/PORTS_OE") (class "Default")
      (node (ref "U1") (pin "2") (pinfunction "PE3_2") (pintype "bidirectional"))
    )
    (net (code "85") (name "/PORTS_RCLK") (class "Default")
      (node (ref "U1") (pin "3") (pinfunction "PE4_3") (pintype "bidirectional"))
    )
    (net (code "86") (name "/PORTS_SER") (class "Default")
      (node (ref "U1") (pin "1") (pinfunction "PE2_1") (pintype "bidirectional"))
    )
    (net (code "87") (name "/PORTS_SRCLK") (class "Default")
      (node (ref "U1") (pin "4") (pinfunction "PE5_4") (pintype "bidirectional"))
    )
    (net (code "88") (name "/PORTS_SRCLR") (class "Default")
      (node (ref "U1") (pin "5") (pinfunction "PE6_5") (pintype "bidirectional"))
    )
    (net (code "89") (name "/RMII_CRS_DV_PA7") (class "Default")
      (node (ref "U1") (pin "43") (pinfunction "PA7_43") (pintype "bidirectional"))
    )
    (net (code "90") (name "/RMII_MDC_PC1") (class "Default")
      (node (ref "U1") (pin "27") (pinfunction "PC1_27") (pintype "bidirectional"))
    )
    (net (code "91") (name "/RMII_MDIO_PA2") (class "Default")
      (node (ref "U1") (pin "36") (pinfunction "PA2_36") (pintype "bidirectional"))
    )
    (net (code "92") (name "/RMII_REF_CLK_PA1") (class "Default")
      (node (ref "U1") (pin "35") (pinfunction "PA1_35") (pintype "bidirectional"))
    )
    (net (code "93") (name "/RMII_RXD_0_PC4") (class "Default")
      (node (ref "U1") (pin "44") (pinfunction "PC4_44") (pintype "bidirectional"))
    )
    (net (code "94") (name "/RMII_RXD_1_PC5") (class "Default")
      (node (ref "U1") (pin "45") (pinfunction "PC5_45") (pintype "bidirectional"))
    )
    (net (code "95") (name "/RMII_TXD_0_PB12") (class "Default")
      (node (ref "U1") (pin "73") (pinfunction "PB12_73") (pintype "bidirectional"))
    )
    (net (code "96") (name "/RMII_TXD_1_PB_13") (class "Default")
      (node (ref "U1") (pin "74") (pinfunction "PB13_74") (pintype "bidirectional"))
    )
    (net (code "97") (name "/RMII_TX_EN_PB11") (class "Default")
      (node (ref "U1") (pin "70") (pinfunction "PB11_70") (pintype "bidirectional"))
    )
    (net (code "98") (name "/SPI2_MISO") (class "Default")
      (node (ref "J16") (pin "1") (pinfunction "1_1") (pintype "passive"))
      (node (ref "U1") (pin "28") (pinfunction "PC2_28") (pintype "bidirectional"))
    )
    (net (code "99") (name "/SPI2_MOSI") (class "Default")
      (node (ref "J16") (pin "3") (pinfunction "3_3") (pintype "passive"))
      (node (ref "U1") (pin "29") (pinfunction "PC3_29") (pintype "bidirectional"))
    )
    (net (code "100") (name "/SPI2_NSS") (class "Default")
      (node (ref "J16") (pin "7") (pinfunction "7_7") (pintype "passive"))
      (node (ref "U1") (pin "140") (pinfunction "PB9_140") (pintype "bidirectional"))
    )
    (net (code "101") (name "/SPI2_SCK") (class "Default")
      (node (ref "J16") (pin "5") (pinfunction "5_5") (pintype "passive"))
      (node (ref "U1") (pin "69") (pinfunction "PB10_69") (pintype "bidirectional"))
    )
    (net (code "102") (name "/STATUS_LED_K") (class "Default")
      (node (ref "D8") (pin "1") (pinfunction "C_1") (pintype "passive"))
      (node (ref "R41") (pin "2") (pinfunction "2_2") (pintype "passive"))
    )
    (net (code "103") (name "/STM_NRTS") (class "Default")
      (node (ref "C19") (pin "1") (pinfunction "1_1") (pintype "passive"))
      (node (ref "J2") (pin "10") (pinfunction "10_10") (pintype "passive"))
      (node (ref "R4") (pin "2") (pinfunction "2_2") (pintype "passive"))
      (node (ref "S1") (pin "2") (pinfunction "A_2") (pintype "passive"))
      (node (ref "U1") (pin "25") (pinfunction "NRST_25") (pintype "bidirectional"))
    )
    (net (code "104") (name "/SWCLK") (class "Default")
      (node (ref "J2") (pin "4") (pinfunction "4_4") (pintype "passive"))
      (node (ref "U1") (pin "109") (pinfunction "PA14(JTCK-SWCLK)_109") (pintype "bidirectional"))
    )
    (net (code "105") (name "/SWDIO") (class "Default")
      (node (ref "J2") (pin "2") (pinfunction "2_2") (pintype "passive"))
      (node (ref "U1") (pin "105") (pinfunction "PA13(JTMS-SWDIO)_105") (pintype "bidirectional"))
    )
    (net (code "106") (name "/SWO") (class "Default")
      (node (ref "J2") (pin "6") (pinfunction "6_6") (pintype "passive"))
      (node (ref "U1") (pin "133") (pinfunction "PB3(JTDO/TRACESWO)_133") (pintype "bidirectional"))
    )
    (net (code "107") (name "/USART2_RX") (class "Default")
      (node (ref "J18") (pin "1") (pinfunction "1_1") (pintype "passive"))
      (node (ref "J18") (pin "2") (pinfunction "2_2") (pintype "passive"))
      (node (ref "U1") (pin "122") (pinfunction "PD6_122") (pintype "bidirectional"))
    )
    (net (code "108") (name "/USART2_TX") (class "Default")
      (node (ref "J17") (pin "1") (pinfunction "1_1") (pintype "passive"))
      (node (ref "J17") (pin "2") (pinfunction "2_2") (pintype "passive"))
      (node (ref "U1") (pin "119") (pinfunction "PD5_119") (pintype "bidirectional"))
    )
    (net (code "109") (name "/USB_5V") (class "Default")
      (node (ref "P8") (pin "3") (pinfunction "3_3") (pintype "passive"))
    )
    (net (code "110") (name "/USB_5V_from_jumper") (class "Default")
      (node (ref "D10") (pin "2") (pinfunction "A_2") (pintype "passive"))
      (node (ref "D4") (pin "2") (pinfunction "A_2") (pintype "passive"))
      (node (ref "P8") (pin "1") (pinfunction "1_1") (pintype "passive"))
      (node (ref "P8") (pin "2") (pinfunction "2_2") (pintype "passive"))
    )
    (net (code "111") (name "/USB_D_N") (class "Default")
      (node (ref "U1") (pin "103") (pinfunction "PA11_103") (pintype "bidirectional"))
    )
    (net (code "112") (name "/USB_D_P") (class "Default")
      (node (ref "U1") (pin "104") (pinfunction "PA12_104") (pintype "bidirectional"))
    )
    (net (code "113") (name "/USB_ID") (class "Default")
      (node (ref "U1") (pin "102") (pinfunction "PA10_102") (pintype "bidirectional"))
    )
    (net (code "114") (name "/USB_SENSE") (class "Default")
      (node (ref "U1") (pin "101") (pinfunction "PA9_101") (pintype "bidirectional"))
    )
    (net (code "115") (name "/VCAP1") (class "Default")
      (node (ref "C17") (pin "1") (pinfunction "1_1") (pintype "passive"))
      (node (ref "U1") (pin "71") (pinfunction "VCAP_1_71") (pintype "power_in"))
    )
    (net (code "116") (name "/VCAP2") (class "Default")
      (node (ref "C16") (pin "1") (pinfunction "1_1") (pintype "passive"))
      (node (ref "U1") (pin "106") (pinfunction "VCAP_2_106") (pintype "power_in"))
    )
    (net (code "117") (name "/V_pin_sense1") (class "Default")
      (node (ref "J1") (pin "30") (pinfunction "30_30") (pintype "passive"))
      (node (ref "U1") (pin "34") (pinfunction "PA0-WKUP(PA0)_34") (pintype "bidirectional"))
    )
    (net (code "118") (name "/V_ref_analog") (class "Default")
      (node (ref "U1") (pin "32") (pinfunction "VREF+_32") (pintype "power_in"))
    )
    (net (code "119") (name "/Vref1") (class "Default")
      (node (ref "J1") (pin "32") (pinfunction "32_32") (pintype "passive"))
      (node (ref "P12") (pin "2") (pinfunction "2_2") (pintype "passive"))
      (node (ref "R47") (pin "2") (pinfunction "2_2") (pintype "passive"))
      (node (ref "U12") (pin "1") (pinfunction "OUT_A_1") (pintype "output"))
      (node (ref "VR1") (pin "2") (pinfunction "WIPER_2") (pintype "passive"))
    )
    (net (code "120") (name "/status_LED") (class "Default")
      (node (ref "D8") (pin "2") (pinfunction "A_2") (pintype "passive"))
      (node (ref "U1") (pin "142") (pinfunction "PE1_142") (pintype "bidirectional"))
    )
    (net (code "121") (name "3V3_MCU") (class "Default")
      (node (ref "C10") (pin "1") (pinfunction "1_1") (pintype "passive"))
      (node (ref "C11") (pin "1") (pinfunction "1_1") (pintype "passive"))
      (node (ref "C12") (pin "1") (pinfunction "1_1") (pintype "passive"))
      (node (ref "C13") (pin "1") (pinfunction "1_1") (pintype "passive"))
      (node (ref "C14") (pin "1") (pinfunction "1_1") (pintype "passive"))
      (node (ref "C15") (pin "1") (pinfunction "1_1") (pintype "passive"))
      (node (ref "C18") (pin "1") (pinfunction "1_1") (pintype "passive"))
      (node (ref "C20") (pin "1") (pinfunction "1_1") (pintype "passive"))
      (node (ref "C3") (pin "1") (pinfunction "1_1") (pintype "passive"))
      (node (ref "C4") (pin "1") (pinfunction "1_1") (pintype "passive"))
      (node (ref "C5") (pin "1") (pinfunction "1_1") (pintype "passive"))
      (node (ref "C6") (pin "1") (pinfunction "1_1") (pintype "passive"))
      (node (ref "C7") (pin "1") (pinfunction "1_1") (pintype "passive"))
      (node (ref "C8") (pin "1") (pinfunction "1_1") (pintype "passive"))
      (node (ref "C9") (pin "1") (pinfunction "1_1") (pintype "passive"))
      (node (ref "J1") (pin "28") (pinfunction "28_28") (pintype "passive"))
      (node (ref "J16") (pin "9") (pinfunction "9_9") (pintype "passive"))
      (node (ref "J2") (pin "1") (pinfunction "1_1") (pintype "passive"))
      (node (ref "P1") (pin "1") (pinfunction "1_1") (pintype "passive"))
      (node (ref "P11") (pin "1") (pinfunction "1_1") (pintype "passive"))
      (node (ref "P2") (pin "1") (pinfunction "1_1") (pintype "passive"))
      (node (ref "R1") (pin "1") (pinfunction "1_1") (pintype "passive"))
      (node (ref "R33") (pin "1") (pinfunction "1_1") (pintype "passive"))
      (node (ref "R36") (pin "1") (pinfunction "1_1") (pintype "passive"))
      (node (ref "R4") (pin "1") (pinfunction "1_1") (pintype "passive"))
      (node (ref "R42") (pin "1") (pinfunction "1_1") (pintype "passive"))
      (node (ref "U1") (pin "108") (pinfunction "VDD_108") (pintype "power_in"))
      (node (ref "U1") (pin "121") (pinfunction "VDD_121") (pintype "power_in"))
      (node (ref "U1") (pin "131") (pinfunction "VDD_131") (pintype "power_in"))
      (node (ref "U1") (pin "144") (pinfunction "VDD_144") (pintype "power_in"))
      (node (ref "U1") (pin "17") (pinfunction "VDD_17") (pintype "power_in"))
      (node (ref "U1") (pin "30") (pinfunction "VDD_30") (pintype "power_in"))
      (node (ref "U1") (pin "33") (pinfunction "VDDA_33") (pintype "power_in"))
      (node (ref "U1") (pin "39") (pinfunction "VDD_39") (pintype "power_in"))
      (node (ref "U1") (pin "52") (pinfunction "VDD_52") (pintype "power_in"))
      (node (ref "U1") (pin "6") (pinfunction "VBAT_6") (pintype "power_in"))
      (node (ref "U1") (pin "62") (pinfunction "VDD_62") (pintype "power_in"))
      (node (ref "U1") (pin "72") (pinfunction "VDD_72") (pintype "power_in"))
      (node (ref "U1") (pin "84") (pinfunction "VDD_84") (pintype "power_in"))
      (node (ref "U1") (pin "95") (pinfunction "VDD_95") (pintype "power_in"))
      (node (ref "U6") (pin "4") (pinfunction "VCC_4") (pintype "power_in"))
      (node (ref "U7") (pin "16") (pinfunction "VDD_16") (pintype "power_in"))
      (node (ref "U8") (pin "3") (pinfunction "VCC_3") (pintype "power_in"))
    )
    (net (code "122") (name "5V") (class "Default")
      (node (ref "J19") (pin "1") (pinfunction "1_1") (pintype "passive"))
      (node (ref "J19") (pin "2") (pinfunction "2_2") (pintype "passive"))
      (node (ref "P11") (pin "3") (pinfunction "3_3") (pintype "passive"))
    )
    (net (code "123") (name "5V_comp") (class "Default")
      (node (ref "D10") (pin "1") (pinfunction "K_1") (pintype "passive"))
      (node (ref "J10") (pin "1") (pinfunction "1_1") (pintype "passive"))
      (node (ref "J10") (pin "2") (pinfunction "2_2") (pintype "passive"))
    )
    (net (code "124") (name "BOARD_PWR") (class "Default")
      (node (ref "D13") (pin "2") (pinfunction "A_2") (pintype "passive"))
      (node (ref "D14") (pin "1") (pinfunction "K_1") (pintype "passive"))
      (node (ref "D4") (pin "1") (pinfunction "K_1") (pintype "passive"))
      (node (ref "J1") (pin "22") (pinfunction "22_22") (pintype "passive"))
      (node (ref "J1") (pin "24") (pinfunction "24_24") (pintype "passive"))
      (node (ref "J1") (pin "26") (pinfunction "26_26") (pintype "passive"))
    )
    (net (code "125") (name "GND") (class "Default")
      (node (ref "C1") (pin "2") (pinfunction "2_2") (pintype "passive"))
      (node (ref "C10") (pin "2") (pinfunction "2_2") (pintype "passive"))
      (node (ref "C11") (pin "2") (pinfunction "2_2") (pintype "passive"))
      (node (ref "C12") (pin "2") (pinfunction "2_2") (pintype "passive"))
      (node (ref "C13") (pin "2") (pinfunction "2_2") (pintype "passive"))
      (node (ref "C14") (pin "2") (pinfunction "2_2") (pintype "passive"))
      (node (ref "C15") (pin "2") (pinfunction "2_2") (pintype "passive"))
      (node (ref "C16") (pin "2") (pinfunction "2_2") (pintype "passive"))
      (node (ref "C17") (pin "2") (pinfunction "2_2") (pintype "passive"))
      (node (ref "C18") (pin "2") (pinfunction "2_2") (pintype "passive"))
      (node (ref "C19") (pin "2") (pinfunction "2_2") (pintype "passive"))
      (node (ref "C2") (pin "1") (pinfunction "1_1") (pintype "passive"))
      (node (ref "C20") (pin "2") (pinfunction "2_2") (pintype "passive"))
      (node (ref "C3") (pin "2") (pinfunction "2_2") (pintype "passive"))
      (node (ref "C4") (pin "2") (pinfunction "2_2") (pintype "passive"))
      (node (ref "C40") (pin "2") (pinfunction "2_2") (pintype "passive"))
      (node (ref "C41") (pin "2") (pinfunction "2_2") (pintype "passive"))
      (node (ref "C42") (pin "2") (pinfunction "2_2") (pintype "passive"))
      (node (ref "C43") (pin "2") (pinfunction "2_2") (pintype "passive"))
      (node (ref "C5") (pin "2") (pinfunction "2_2") (pintype "passive"))
      (node (ref "C6") (pin "2") (pinfunction "2_2") (pintype "passive"))
      (node (ref "C7") (pin "2") (pinfunction "2_2") (pintype "passive"))
      (node (ref "C8") (pin "2") (pinfunction "2_2") (pintype "passive"))
      (node (ref "C9") (pin "2") (pinfunction "2_2") (pintype "passive"))
      (node (ref "J1") (pin "34") (pinfunction "34_34") (pintype "passive"))
      (node (ref "J1") (pin "36") (pinfunction "36_36") (pintype "passive"))
      (node (ref "J1") (pin "38") (pinfunction "38_38") (pintype "passive"))
      (node (ref "J1") (pin "40") (pinfunction "40_40") (pintype "passive"))
      (node (ref "J14") (pin "1") (pinfunction "1_1") (pintype "passive"))
      (node (ref "J14") (pin "2") (pinfunction "2_2") (pintype "passive"))
      (node (ref "J16") (pin "10") (pinfunction "10_10") (pintype "passive"))
      (node (ref "J16") (pin "2") (pinfunction "2_2") (pintype "passive"))
      (node (ref "J16") (pin "4") (pinfunction "4_4") (pintype "passive"))
      (node (ref "J16") (pin "6") (pinfunction "6_6") (pintype "passive"))
      (node (ref "J16") (pin "8") (pinfunction "8_8") (pintype "passive"))
      (node (ref "J2") (pin "3") (pinfunction "3_3") (pintype "passive"))
      (node (ref "J2") (pin "5") (pinfunction "5_5") (pintype "passive"))
      (node (ref "J2") (pin "9") (pinfunction "9_9") (pintype "passive"))
      (node (ref "J5") (pin "1") (pinfunction "1_1") (pintype "passive"))
      (node (ref "J5") (pin "2") (pinfunction "2_2") (pintype "passive"))
      (node (ref "P1") (pin "3") (pinfunction "3_3") (pintype "passive"))
      (node (ref "P2") (pin "3") (pinfunction "3_3") (pintype "passive"))
      (node (ref "P3") (pin "2") (pinfunction "2_2") (pintype "passive"))
      (node (ref "P9") (pin "3") (pinfunction "3_3") (pintype "passive"))
      (node (ref "R41") (pin "1") (pinfunction "1_1") (pintype "passive"))
      (node (ref "R48") (pin "1") (pinfunction "1_1") (pintype "passive"))
      (node (ref "R50") (pin "1") (pinfunction "1_1") (pintype "passive"))
      (node (ref "R51") (pin "1") (pinfunction "1_1") (pintype "passive"))
      (node (ref "S1") (pin "1") (pinfunction "K_1") (pintype "passive"))
      (node (ref "U1") (pin "107") (pinfunction "VSS_107") (pintype "power_in"))
      (node (ref "U1") (pin "120") (pinfunction "VSS_120") (pintype "power_in"))
      (node (ref "U1") (pin "130") (pinfunction "VSS_130") (pintype "power_in"))
      (node (ref "U1") (pin "16") (pinfunction "VSS_16") (pintype "power_in"))
      (node (ref "U1") (pin "31") (pinfunction "VSSA_31") (pintype "power_in"))
      (node (ref "U1") (pin "38") (pinfunction "VSS_38") (pintype "power_in"))
      (node (ref "U1") (pin "51") (pinfunction "VSS_51") (pintype "power_in"))
      (node (ref "U1") (pin "61") (pinfunction "VSS_61") (pintype "power_in"))
      (node (ref "U1") (pin "83") (pinfunction "VSS_83") (pintype "power_in"))
      (node (ref "U1") (pin "94") (pinfunction "VSS_94") (pintype "power_in"))
      (node (ref "U12") (pin "8") (pinfunction "+V_8") (pintype "power_in"))
      (node (ref "U6") (pin "2") (pinfunction "GND_2") (pintype "power_in"))
      (node (ref "U7") (pin "8") (pinfunction "GND_8") (pintype "power_in"))
      (node (ref "U8") (pin "2") (pinfunction "GND_2") (pintype "power_in"))
      (node (ref "VR4") (pin "1") (pinfunction "CCW_1") (pintype "passive"))
      (node (ref "VR5") (pin "1") (pinfunction "CCW_1") (pintype "passive"))
      (node (ref "Y1") (pin "2") (pinfunction "GND_2") (pintype "power_in"))
      (node (ref "Y1") (pin "4") (pinfunction "GND_4") (pintype "power_in"))
    )
    (net (code "126") (name "Net-(VR1-CCW)") (class "Default")
      (node (ref "C40") (pin "1") (pinfunction "1_1") (pintype "passive"))
      (node (ref "VR1") (pin "1") (pinfunction "CCW_1") (pintype "passive"))
    )
    (net (code "127") (name "Net-(VR3-CCW)") (class "Default")
      (node (ref "C43") (pin "1") (pinfunction "1_1") (pintype "passive"))
      (node (ref "VR3") (pin "1") (pinfunction "CCW_1") (pintype "passive"))
    )
    (net (code "128") (name "unconnected-(J2-Pad7)") (class "Default")
      (node (ref "J2") (pin "7") (pinfunction "7_7") (pintype "passive"))
    )
    (net (code "129") (name "unconnected-(J2-Pad8)") (class "Default")
      (node (ref "J2") (pin "8") (pinfunction "8_8") (pintype "passive"))
    )
    (net (code "130") (name "unconnected-(U1A-PA8-Pad100)") (class "Default")
      (node (ref "U1") (pin "100") (pinfunction "PA8_100") (pintype "bidirectional"))
    )
    (net (code "131") (name "unconnected-(U1A-PB4(NJTRST)-Pad134)") (class "Default")
      (node (ref "U1") (pin "134") (pinfunction "PB4(NJTRST)_134") (pintype "bidirectional"))
    )
    (net (code "132") (name "unconnected-(U1A-PB8-Pad139)") (class "Default")
      (node (ref "U1") (pin "139") (pinfunction "PB8_139") (pintype "bidirectional"))
    )
    (net (code "133") (name "unconnected-(U1A-PC13-Pad7)") (class "Default")
      (node (ref "U1") (pin "7") (pinfunction "PC13_7") (pintype "bidirectional"))
    )
    (net (code "134") (name "unconnected-(U1A-PD3-Pad117)") (class "Default")
      (node (ref "U1") (pin "117") (pinfunction "PD3_117") (pintype "bidirectional"))
    )
    (net (code "135") (name "unconnected-(U1A-PD4-Pad118)") (class "Default")
      (node (ref "U1") (pin "118") (pinfunction "PD4_118") (pintype "bidirectional"))
    )
    (net (code "136") (name "unconnected-(U1A-PD7-Pad123)") (class "Default")
      (node (ref "U1") (pin "123") (pinfunction "PD7_123") (pintype "bidirectional"))
    )
    (net (code "137") (name "unconnected-(U1B-PE0-Pad141)") (class "Default")
      (node (ref "U1") (pin "141") (pinfunction "PE0_141") (pintype "bidirectional"))
    )
    (net (code "138") (name "unconnected-(U1B-PE8-Pad59)") (class "Default")
      (node (ref "U1") (pin "59") (pinfunction "PE8_59") (pintype "bidirectional"))
    )
    (net (code "139") (name "unconnected-(U1B-PE9-Pad60)") (class "Default")
      (node (ref "U1") (pin "60") (pinfunction "PE9_60") (pintype "bidirectional"))
    )
    (net (code "140") (name "unconnected-(U1B-PE10-Pad63)") (class "Default")
      (node (ref "U1") (pin "63") (pinfunction "PE10_63") (pintype "bidirectional"))
    )
    (net (code "141") (name "unconnected-(U1B-PF3-Pad13)") (class "Default")
      (node (ref "U1") (pin "13") (pinfunction "PF3_13") (pintype "bidirectional"))
    )
    (net (code "142") (name "unconnected-(U1B-PF4-Pad14)") (class "Default")
      (node (ref "U1") (pin "14") (pinfunction "PF4_14") (pintype "bidirectional"))
    )
    (net (code "143") (name "unconnected-(U1B-PF7-Pad19)") (class "Default")
      (node (ref "U1") (pin "19") (pinfunction "PF7_19") (pintype "bidirectional"))
    )
    (net (code "144") (name "unconnected-(U1B-PF9-Pad21)") (class "Default")
      (node (ref "U1") (pin "21") (pinfunction "PF9_21") (pintype "bidirectional"))
    )
    (net (code "145") (name "unconnected-(U1B-PF10-Pad22)") (class "Default")
      (node (ref "U1") (pin "22") (pinfunction "PF10_22") (pintype "bidirectional"))
    )
    (net (code "146") (name "unconnected-(U1B-PF13-Pad53)") (class "Default")
      (node (ref "U1") (pin "53") (pinfunction "PF13_53") (pintype "bidirectional"))
    )
    (net (code "147") (name "unconnected-(U1B-PF15-Pad55)") (class "Default")
      (node (ref "U1") (pin "55") (pinfunction "PF15_55") (pintype "bidirectional"))
    )
    (net (code "148") (name "unconnected-(U1B-PG9-Pad124)") (class "Default")
      (node (ref "U1") (pin "124") (pinfunction "PG9_124") (pintype "bidirectional"))
    )
    (net (code "149") (name "unconnected-(U1B-PG10-Pad125)") (class "Default")
      (node (ref "U1") (pin "125") (pinfunction "PG10_125") (pintype "bidirectional"))
    )
    (net (code "150") (name "unconnected-(U1B-PG11-Pad126)") (class "Default")
      (node (ref "U1") (pin "126") (pinfunction "PG11_126") (pintype "bidirectional"))
    )
    (net (code "151") (name "unconnected-(U1B-PG12-Pad127)") (class "Default")
      (node (ref "U1") (pin "127") (pinfunction "PG12_127") (pintype "bidirectional"))
    )
    (net (code "152") (name "unconnected-(U1B-PG13-Pad128)") (class "Default")
      (node (ref "U1") (pin "128") (pinfunction "PG13_128") (pintype "bidirectional"))
    )
    (net (code "153") (name "unconnected-(U1B-PG14-Pad129)") (class "Default")
      (node (ref "U1") (pin "129") (pinfunction "PG14_129") (pintype "bidirectional"))
    )
    (net (code "154") (name "unconnected-(U1B-PG15-Pad132)") (class "Default")
      (node (ref "U1") (pin "132") (pinfunction "PG15_132") (pintype "bidirectional"))
    )
    (net (code "155") (name "unconnected-(U7-NC-Pad7)") (class "Default")
      (node (ref "U7") (pin "7") (pinfunction "NC_7") (pintype "passive"))
    )
    (net (code "156") (name "unconnected-(U8-NC-Pad5)") (class "Default")
      (node (ref "U8") (pin "5") (pinfunction "NC_5") (pintype "passive"))
    )
    (net (code "157") (name "unconnected-(U8-NC-Pad8)") (class "Default")
      (node (ref "U8") (pin "8") (pinfunction "NC_8") (pintype "passive"))
    )
    (net (code "158") (name "unconnected-(VR1-CW-Pad3)") (class "Default")
      (node (ref "VR1") (pin "3") (pinfunction "CW_3") (pintype "passive"))
    )
    (net (code "159") (name "unconnected-(VR3-CW-Pad3)") (class "Default")
      (node (ref "VR3") (pin "3") (pinfunction "CW_3") (pintype "passive"))
    )
  )
)
